# nusense-power-decoupling.net
KiCad netlist of a schematic drawn in Altium Designer
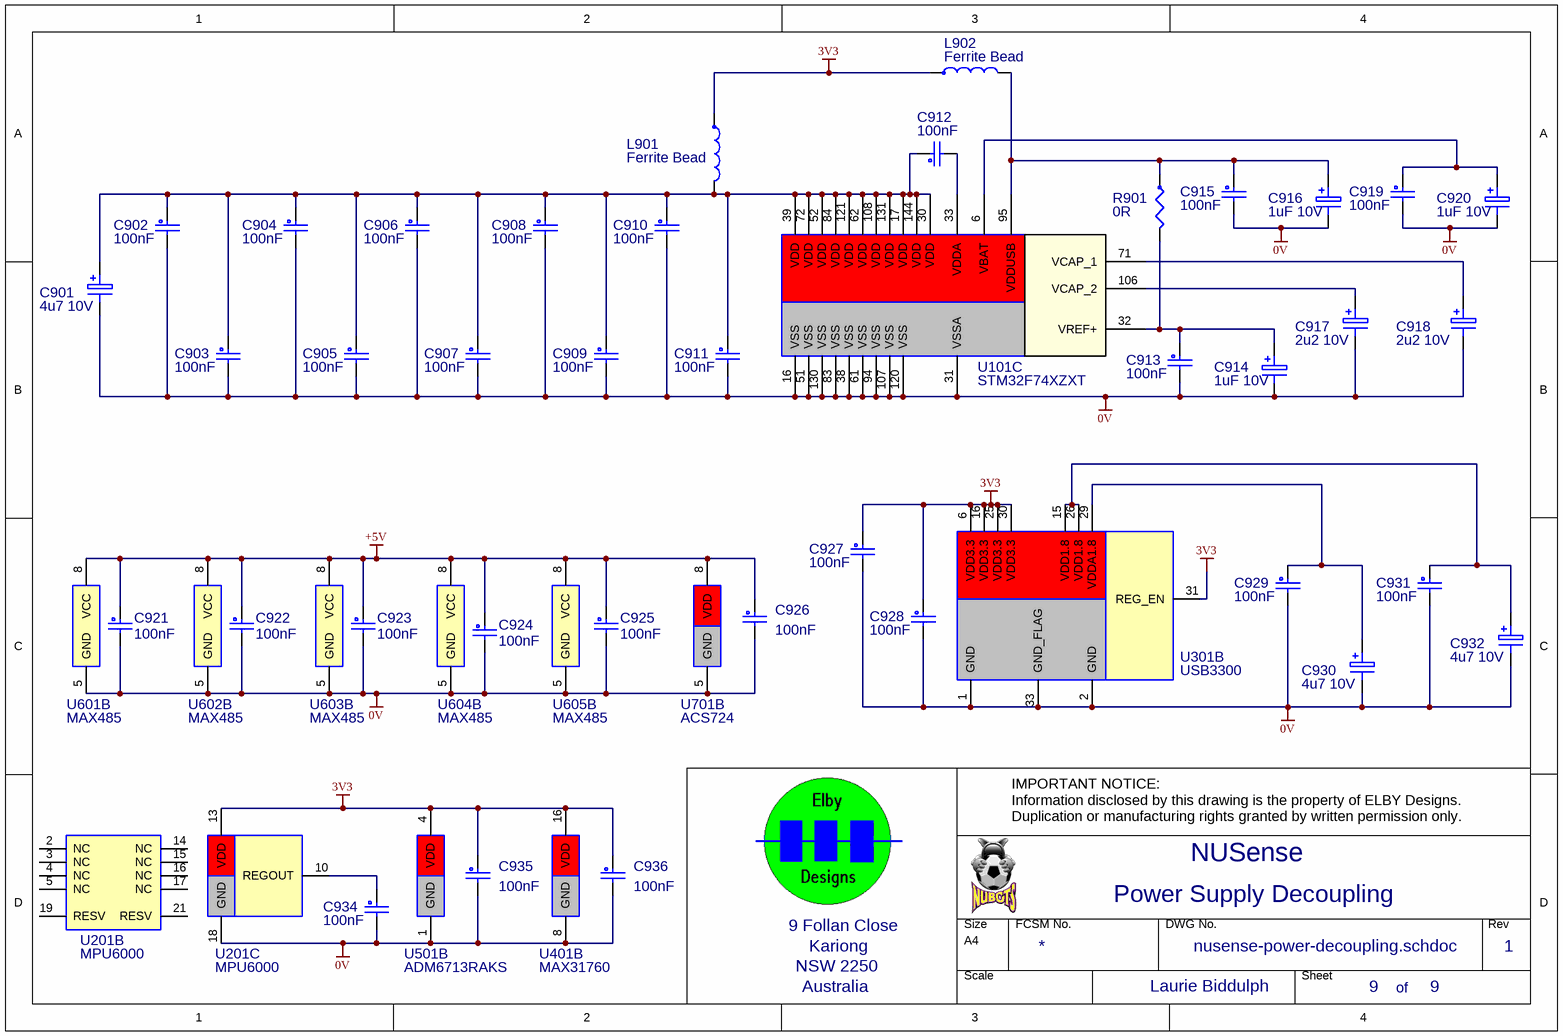
[diagram p0: nusense-power-decoupling.schdoc]

(export (version "E")
  (design (tool "Eeschema 10.0.6"))
  (components
    (comp (ref "C901")
      (value "4u7 10V")
      (footprint "RB-D5.0-P2.0")
      (description "20% 50V Aluminium Electrolytic")
      (libsource (lib "capacitor") (part "CE-4U7F50V(LB)"))
    )
    (comp (ref "C902")
      (value "100nF")
      (footprint "RAD-0.2N(LB)")
      (description "Monolithic Ceramic")
      (libsource (lib "capacitor") (part "CC-100NF(LB)"))
    )
    (comp (ref "C903")
      (value "100nF")
      (footprint "RAD-0.2N(LB)")
      (description "Monolithic Ceramic")
      (libsource (lib "capacitor") (part "CC-100NF(LB)"))
    )
    (comp (ref "C904")
      (value "100nF")
      (footprint "RAD-0.2N(LB)")
      (description "Monolithic Ceramic")
      (libsource (lib "capacitor") (part "CC-100NF(LB)"))
    )
    (comp (ref "C905")
      (value "100nF")
      (footprint "RAD-0.2N(LB)")
      (description "Monolithic Ceramic")
      (libsource (lib "capacitor") (part "CC-100NF(LB)"))
    )
    (comp (ref "C906")
      (value "100nF")
      (footprint "RAD-0.2N(LB)")
      (description "Monolithic Ceramic")
      (libsource (lib "capacitor") (part "CC-100NF(LB)"))
    )
    (comp (ref "C907")
      (value "100nF")
      (footprint "RAD-0.2N(LB)")
      (description "Monolithic Ceramic")
      (libsource (lib "capacitor") (part "CC-100NF(LB)"))
    )
    (comp (ref "C908")
      (value "100nF")
      (footprint "RAD-0.2N(LB)")
      (description "Monolithic Ceramic")
      (libsource (lib "capacitor") (part "CC-100NF(LB)"))
    )
    (comp (ref "C909")
      (value "100nF")
      (footprint "RAD-0.2N(LB)")
      (description "Monolithic Ceramic")
      (libsource (lib "capacitor") (part "CC-100NF(LB)"))
    )
    (comp (ref "C910")
      (value "100nF")
      (footprint "RAD-0.2N(LB)")
      (description "Monolithic Ceramic")
      (libsource (lib "capacitor") (part "CC-100NF(LB)"))
    )
    (comp (ref "C911")
      (value "100nF")
      (footprint "RAD-0.2N(LB)")
      (description "Monolithic Ceramic")
      (libsource (lib "capacitor") (part "CC-100NF(LB)"))
    )
    (comp (ref "C912")
      (value "100nF")
      (footprint "RAD-0.2N(LB)")
      (description "Monolithic Ceramic")
      (libsource (lib "capacitor") (part "CC-100NF(LB)"))
    )
    (comp (ref "C913")
      (value "100nF")
      (footprint "RAD-0.2N(LB)")
      (description "Monolithic Ceramic")
      (libsource (lib "capacitor") (part "CC-100NF(LB)"))
    )
    (comp (ref "C914")
      (value "1uF 10V")
      (footprint "RB-D5.0-P2.0")
      (description "20% 50V Aluminium Electrolytic")
      (libsource (lib "capacitor") (part "CE-1UF50V(LB)"))
    )
    (comp (ref "C915")
      (value "100nF")
      (footprint "RAD-0.2N(LB)")
      (description "Monolithic Ceramic")
      (libsource (lib "capacitor") (part "CC-100NF(LB)"))
    )
    (comp (ref "C916")
      (value "1uF 10V")
      (footprint "RB-D5.0-P2.0")
      (description "20% 50V Aluminium Electrolytic")
      (libsource (lib "capacitor") (part "CE-1UF50V(LB)"))
    )
    (comp (ref "C917")
      (value "2u2 10V")
      (footprint "RB-D5.0-P2.0")
      (description "20% 50V Aluminium Electrolytic")
      (libsource (lib "capacitor") (part "CE-2U2F50V(LB)"))
    )
    (comp (ref "C918")
      (value "2u2 10V")
      (footprint "RB-D5.0-P2.0")
      (description "20% 50V Aluminium Electrolytic")
      (libsource (lib "capacitor") (part "CE-2U2F50V(LB)"))
    )
    (comp (ref "C919")
      (value "100nF")
      (footprint "RAD-0.2N(LB)")
      (description "Monolithic Ceramic")
      (libsource (lib "capacitor") (part "CC-100NF(LB)"))
    )
    (comp (ref "C920")
      (value "1uF 10V")
      (footprint "RB-D5.0-P2.0")
      (description "20% 50V Aluminium Electrolytic")
      (libsource (lib "capacitor") (part "CE-1UF50V(LB)"))
    )
    (comp (ref "C921")
      (value "100nF")
      (footprint "RAD-0.2N(LB)")
      (description "Monolithic Ceramic")
      (libsource (lib "capacitor") (part "CC-100NF(LB)"))
    )
    (comp (ref "C922")
      (value "100nF")
      (footprint "RAD-0.2N(LB)")
      (description "Monolithic Ceramic")
      (libsource (lib "capacitor") (part "CC-100NF(LB)"))
    )
    (comp (ref "C923")
      (value "100nF")
      (footprint "RAD-0.2N(LB)")
      (description "Monolithic Ceramic")
      (libsource (lib "capacitor") (part "CC-100NF(LB)"))
    )
    (comp (ref "C924")
      (value "100nF")
      (footprint "RAD-0.2N(LB)")
      (description "Monolithic Ceramic")
      (libsource (lib "capacitor") (part "CC-100NF(LB)"))
    )
    (comp (ref "C925")
      (value "100nF")
      (footprint "RAD-0.2N(LB)")
      (description "Monolithic Ceramic")
      (libsource (lib "capacitor") (part "CC-100NF(LB)"))
    )
    (comp (ref "C926")
      (value "100nF")
      (footprint "RAD-0.2N(LB)")
      (description "Monolithic Ceramic")
      (libsource (lib "capacitor") (part "CC-100NF(LB)"))
    )
    (comp (ref "C927")
      (value "100nF")
      (footprint "RAD-0.2N(LB)")
      (description "Monolithic Ceramic")
      (libsource (lib "capacitor") (part "CC-100NF(LB)"))
    )
    (comp (ref "C928")
      (value "100nF")
      (footprint "RAD-0.2N(LB)")
      (description "Monolithic Ceramic")
      (libsource (lib "capacitor") (part "CC-100NF(LB)"))
    )
    (comp (ref "C929")
      (value "100nF")
      (footprint "RAD-0.2N(LB)")
      (description "Monolithic Ceramic")
      (libsource (lib "capacitor") (part "CC-100NF(LB)"))
    )
    (comp (ref "C930")
      (value "4u7 10V")
      (footprint "RB-D5.0-P2.0")
      (description "20% 50V Aluminium Electrolytic")
      (libsource (lib "capacitor") (part "CE-4U7F50V(LB)"))
    )
    (comp (ref "C931")
      (value "100nF")
      (footprint "RAD-0.2N(LB)")
      (description "Monolithic Ceramic")
      (libsource (lib "capacitor") (part "CC-100NF(LB)"))
    )
    (comp (ref "C932")
      (value "4u7 10V")
      (footprint "RB-D5.0-P2.0")
      (description "20% 50V Aluminium Electrolytic")
      (libsource (lib "capacitor") (part "CE-4U7F50V(LB)"))
    )
    (comp (ref "C934")
      (value "100nF")
      (footprint "RAD-0.2N(LB)")
      (description "Monolithic Ceramic")
      (libsource (lib "capacitor") (part "CC-100NF(LB)"))
    )
    (comp (ref "C935")
      (value "100nF")
      (footprint "RAD-0.2N(LB)")
      (description "Monolithic Ceramic")
      (libsource (lib "capacitor") (part "CC-100NF(LB)"))
    )
    (comp (ref "C936")
      (value "100nF")
      (footprint "RAD-0.2N(LB)")
      (description "Monolithic Ceramic")
      (libsource (lib "capacitor") (part "CC-100NF(LB)"))
    )
    (comp (ref "L901")
      (value "Ferrite Bead")
      (footprint "AXIAL-0.3IND(LB)")
      (libsource (lib "") (part "FERRITE-BEAD(LB)_1"))
    )
    (comp (ref "L902")
      (value "Ferrite Bead")
      (footprint "AXIAL-0.3IND(LB)")
      (libsource (lib "passive") (part "FERRITE-BEAD(LB)"))
    )
    (comp (ref "R901")
      (value "0R")
      (footprint "AXIAL-0.4(LB)")
      (description "Resistor - Short Circuit")
      (libsource (lib "resistor") (part "RM-SC(LB)"))
    )
    (comp (ref "U101")
      (value "STM32F74XZXT")
      (footprint "LQFP-144_20X20mm")
      (description "32-bit Microcontroller")
      (fields
        (field (name "MANUFACTURER_PART_NUMBER") "stm32f74xzxt")
        (field (name "COPYRIGHT") "Copyright (C) 2016 Accelerated Designs. All rights reserved")
      )
      (libsource (lib "NuBots") (part "STM32F74XZXT"))
    )
    (comp (ref "U201")
      (value "MPU6000")
      (description "Motion Tracking")
      (libsource (lib "NuBots") (part "MPU6000"))
    )
    (comp (ref "U301")
      (value "USB3300")
      (footprint "QFN-32_L")
      (description "USB Host Controller")
      (libsource (lib "NuBots") (part "USB3300"))
    )
    (comp (ref "U401")
      (value "MAX31760")
      (description "Precision Fan Speed")
      (libsource (lib "NuBots") (part "MAX31760"))
    )
    (comp (ref "U501") (value "ADM6713RAKS") (libsource (lib "NuBots") (part "ADM6713")))
    (comp (ref "U601")
      (value "MAX485")
      (footprint "DIP-8(LB)")
      (description "Low-power, Slew-rate limited RS485/RS422 Transceiver")
      (libsource (lib "ic") (part "MAX485(LB)"))
    )
    (comp (ref "U602")
      (value "MAX485")
      (footprint "DIP-8(LB)")
      (description "Low-power, Slew-rate limited RS485/RS422 Transceiver")
      (libsource (lib "ic") (part "MAX485(LB)"))
    )
    (comp (ref "U603")
      (value "MAX485")
      (footprint "DIP-8(LB)")
      (description "Low-power, Slew-rate limited RS485/RS422 Transceiver")
      (libsource (lib "ic") (part "MAX485(LB)"))
    )
    (comp (ref "U604")
      (value "MAX485")
      (footprint "DIP-8(LB)")
      (description "Low-power, Slew-rate limited RS485/RS422 Transceiver")
      (libsource (lib "ic") (part "MAX485(LB)"))
    )
    (comp (ref "U605")
      (value "MAX485")
      (footprint "DIP-8(LB)")
      (description "Low-power, Slew-rate limited RS485/RS422 Transceiver")
      (libsource (lib "ic") (part "MAX485(LB)"))
    )
    (comp (ref "U701")
      (value "ACS724")
      (description "Current Monitor")
      (libsource (lib "NuBots") (part "ACS724"))
    )
  )
  (nets
    (net (code "1") (name "+5V") (class "Default")
      (node (ref "C921") (pin "1") (pintype "passive"))
      (node (ref "C922") (pin "1") (pintype "passive"))
      (node (ref "C923") (pin "1") (pintype "passive"))
      (node (ref "C924") (pin "1") (pintype "passive"))
      (node (ref "C925") (pin "1") (pintype "passive"))
      (node (ref "C926") (pin "1") (pintype "passive"))
      (node (ref "U601") (pin "8") (pinfunction "VCC_8") (pintype "power_in"))
      (node (ref "U602") (pin "8") (pinfunction "VCC_8") (pintype "power_in"))
      (node (ref "U603") (pin "8") (pinfunction "VCC_8") (pintype "power_in"))
      (node (ref "U604") (pin "8") (pinfunction "VCC_8") (pintype "power_in"))
      (node (ref "U605") (pin "8") (pinfunction "VCC_8") (pintype "power_in"))
      (node (ref "U701") (pin "8") (pinfunction "VDD_8") (pintype "power_in"))
    )
    (net (code "2") (name "0V") (class "Default")
      (node (ref "C901") (pin "2") (pintype "passive"))
      (node (ref "C902") (pin "2") (pintype "passive"))
      (node (ref "C903") (pin "2") (pintype "passive"))
      (node (ref "C904") (pin "2") (pintype "passive"))
      (node (ref "C905") (pin "2") (pintype "passive"))
      (node (ref "C906") (pin "2") (pintype "passive"))
      (node (ref "C907") (pin "2") (pintype "passive"))
      (node (ref "C908") (pin "2") (pintype "passive"))
      (node (ref "C909") (pin "2") (pintype "passive"))
      (node (ref "C910") (pin "2") (pintype "passive"))
      (node (ref "C911") (pin "2") (pintype "passive"))
      (node (ref "C913") (pin "2") (pintype "passive"))
      (node (ref "C914") (pin "2") (pintype "passive"))
      (node (ref "C915") (pin "2") (pintype "passive"))
      (node (ref "C916") (pin "2") (pintype "passive"))
      (node (ref "C917") (pin "2") (pintype "passive"))
      (node (ref "C918") (pin "2") (pintype "passive"))
      (node (ref "C919") (pin "2") (pintype "passive"))
      (node (ref "C920") (pin "2") (pintype "passive"))
      (node (ref "C921") (pin "2") (pintype "passive"))
      (node (ref "C922") (pin "2") (pintype "passive"))
      (node (ref "C923") (pin "2") (pintype "passive"))
      (node (ref "C924") (pin "2") (pintype "passive"))
      (node (ref "C925") (pin "2") (pintype "passive"))
      (node (ref "C926") (pin "2") (pintype "passive"))
      (node (ref "C927") (pin "2") (pintype "passive"))
      (node (ref "C928") (pin "2") (pintype "passive"))
      (node (ref "C929") (pin "2") (pintype "passive"))
      (node (ref "C930") (pin "2") (pintype "passive"))
      (node (ref "C931") (pin "2") (pintype "passive"))
      (node (ref "C932") (pin "2") (pintype "passive"))
      (node (ref "C934") (pin "2") (pintype "passive"))
      (node (ref "C935") (pin "2") (pintype "passive"))
      (node (ref "C936") (pin "2") (pintype "passive"))
      (node (ref "U101") (pin "107") (pinfunction "VSS_107") (pintype "power_in"))
      (node (ref "U101") (pin "120") (pinfunction "VSS_120") (pintype "power_in"))
      (node (ref "U101") (pin "130") (pinfunction "VSS_130") (pintype "power_in"))
      (node (ref "U101") (pin "16") (pinfunction "VSS_16") (pintype "power_in"))
      (node (ref "U101") (pin "31") (pinfunction "VSSA_31") (pintype "power_in"))
      (node (ref "U101") (pin "38") (pinfunction "VSS_38") (pintype "power_in"))
      (node (ref "U101") (pin "51") (pinfunction "VSS_51") (pintype "power_in"))
      (node (ref "U101") (pin "61") (pinfunction "VSS_61") (pintype "power_in"))
      (node (ref "U101") (pin "83") (pinfunction "VSS_83") (pintype "power_in"))
      (node (ref "U101") (pin "94") (pinfunction "VSS_94") (pintype "power_in"))
      (node (ref "U201") (pin "18") (pinfunction "GND_18") (pintype "power_in"))
      (node (ref "U301") (pin "1") (pinfunction "GND_1") (pintype "power_in"))
      (node (ref "U301") (pin "2") (pinfunction "GND_2") (pintype "power_in"))
      (node (ref "U301") (pin "33") (pinfunction "GND_FLAG_33") (pintype "power_in"))
      (node (ref "U401") (pin "8") (pinfunction "GND_8") (pintype "power_in"))
      (node (ref "U501") (pin "1") (pinfunction "GND_1") (pintype "power_in"))
      (node (ref "U601") (pin "5") (pinfunction "GND_5") (pintype "power_in"))
      (node (ref "U602") (pin "5") (pinfunction "GND_5") (pintype "power_in"))
      (node (ref "U603") (pin "5") (pinfunction "GND_5") (pintype "power_in"))
      (node (ref "U604") (pin "5") (pinfunction "GND_5") (pintype "power_in"))
      (node (ref "U605") (pin "5") (pinfunction "GND_5") (pintype "power_in"))
      (node (ref "U701") (pin "5") (pinfunction "GND_5") (pintype "power_in"))
    )
    (net (code "3") (name "3V3") (class "Default")
      (node (ref "C927") (pin "1") (pintype "passive"))
      (node (ref "C928") (pin "1") (pintype "passive"))
      (node (ref "C935") (pin "1") (pintype "passive"))
      (node (ref "C936") (pin "1") (pintype "passive"))
      (node (ref "L901") (pin "1") (pinfunction "1_1") (pintype "passive"))
      (node (ref "L902") (pin "1") (pinfunction "1_1") (pintype "passive"))
      (node (ref "U201") (pin "13") (pinfunction "VDD_13") (pintype "power_in"))
      (node (ref "U301") (pin "16") (pinfunction "VDD3.3_16") (pintype "power_in"))
      (node (ref "U301") (pin "25") (pinfunction "VDD3.3_25") (pintype "power_in"))
      (node (ref "U301") (pin "30") (pinfunction "VDD3.3_30") (pintype "power_in"))
      (node (ref "U301") (pin "31") (pinfunction "REG_EN_31") (pintype "passive"))
      (node (ref "U301") (pin "6") (pinfunction "VDD3.3_6") (pintype "power_in"))
      (node (ref "U401") (pin "16") (pinfunction "VDD_16") (pintype "power_in"))
      (node (ref "U501") (pin "4") (pinfunction "VDD_4") (pintype "power_in"))
    )
    (net (code "4") (name "Net-(C901-Pad1)") (class "Default")
      (node (ref "C901") (pin "1") (pintype "passive"))
      (node (ref "C902") (pin "1") (pintype "passive"))
      (node (ref "C903") (pin "1") (pintype "passive"))
      (node (ref "C904") (pin "1") (pintype "passive"))
      (node (ref "C905") (pin "1") (pintype "passive"))
      (node (ref "C906") (pin "1") (pintype "passive"))
      (node (ref "C907") (pin "1") (pintype "passive"))
      (node (ref "C908") (pin "1") (pintype "passive"))
      (node (ref "C909") (pin "1") (pintype "passive"))
      (node (ref "C910") (pin "1") (pintype "passive"))
      (node (ref "C911") (pin "1") (pintype "passive"))
      (node (ref "C912") (pin "1") (pintype "passive"))
      (node (ref "L901") (pin "2") (pinfunction "2_2") (pintype "passive"))
      (node (ref "U101") (pin "108") (pinfunction "VDD_108") (pintype "power_in"))
      (node (ref "U101") (pin "121") (pinfunction "VDD_121") (pintype "power_in"))
      (node (ref "U101") (pin "131") (pinfunction "VDD_131") (pintype "power_in"))
      (node (ref "U101") (pin "144") (pinfunction "VDD_144") (pintype "power_in"))
      (node (ref "U101") (pin "17") (pinfunction "VDD_17") (pintype "power_in"))
      (node (ref "U101") (pin "30") (pinfunction "VDD_30") (pintype "power_in"))
      (node (ref "U101") (pin "39") (pinfunction "VDD_39") (pintype "power_in"))
      (node (ref "U101") (pin "52") (pinfunction "VDD_52") (pintype "power_in"))
      (node (ref "U101") (pin "62") (pinfunction "VDD_62") (pintype "power_in"))
      (node (ref "U101") (pin "72") (pinfunction "VDD_72") (pintype "power_in"))
      (node (ref "U101") (pin "84") (pinfunction "VDD_84") (pintype "power_in"))
    )
    (net (code "5") (name "Net-(C931-Pad1)") (class "Default")
      (node (ref "C931") (pin "1") (pintype "passive"))
      (node (ref "C932") (pin "1") (pintype "passive"))
      (node (ref "U301") (pin "15") (pinfunction "VDD1.8_15") (pintype "power_in"))
      (node (ref "U301") (pin "26") (pinfunction "VDD1.8_26") (pintype "power_in"))
    )
    (net (code "6") (name "Net-(U101C-VBAT)") (class "Default")
      (node (ref "C919") (pin "1") (pintype "passive"))
      (node (ref "C920") (pin "1") (pintype "passive"))
      (node (ref "U101") (pin "6") (pinfunction "VBAT_6") (pintype "power_in"))
    )
    (net (code "7") (name "Net-(U101C-VCAP_1)") (class "Default")
      (node (ref "C918") (pin "1") (pintype "passive"))
      (node (ref "U101") (pin "71") (pinfunction "VCAP_1_71") (pintype "power_in"))
    )
    (net (code "8") (name "Net-(U101C-VCAP_2)") (class "Default")
      (node (ref "C917") (pin "1") (pintype "passive"))
      (node (ref "U101") (pin "106") (pinfunction "VCAP_2_106") (pintype "power_in"))
    )
    (net (code "9") (name "Net-(U101C-VDDA)") (class "Default")
      (node (ref "C912") (pin "2") (pintype "passive"))
      (node (ref "U101") (pin "33") (pinfunction "VDDA_33") (pintype "power_in"))
    )
    (net (code "10") (name "Net-(U101C-VDDUSB)") (class "Default")
      (node (ref "C915") (pin "1") (pintype "passive"))
      (node (ref "C916") (pin "1") (pintype "passive"))
      (node (ref "L902") (pin "2") (pinfunction "2_2") (pintype "passive"))
      (node (ref "R901") (pin "1") (pinfunction "1_1") (pintype "passive"))
      (node (ref "U101") (pin "95") (pinfunction "VDDUSB_95") (pintype "power_in"))
    )
    (net (code "11") (name "Net-(U101C-VREF+)") (class "Default")
      (node (ref "C913") (pin "1") (pintype "passive"))
      (node (ref "C914") (pin "1") (pintype "passive"))
      (node (ref "R901") (pin "2") (pinfunction "2_2") (pintype "passive"))
      (node (ref "U101") (pin "32") (pinfunction "VREF+_32") (pintype "power_in"))
    )
    (net (code "12") (name "Net-(U201C-REGOUT)") (class "Default")
      (node (ref "C934") (pin "1") (pintype "passive"))
      (node (ref "U201") (pin "10") (pinfunction "REGOUT_10") (pintype "passive"))
    )
    (net (code "13") (name "Net-(U301B-VDDA1.8)") (class "Default")
      (node (ref "C929") (pin "1") (pintype "passive"))
      (node (ref "C930") (pin "1") (pintype "passive"))
      (node (ref "U301") (pin "29") (pinfunction "VDDA1.8_29") (pintype "power_in"))
    )
    (net (code "14") (name "unconnected-(U201B-NC-Pad2)") (class "Default")
      (node (ref "U201") (pin "2") (pinfunction "NC_2") (pintype "passive"))
    )
    (net (code "15") (name "unconnected-(U201B-NC-Pad3)") (class "Default")
      (node (ref "U201") (pin "3") (pinfunction "NC_3") (pintype "passive"))
    )
    (net (code "16") (name "unconnected-(U201B-NC-Pad4)") (class "Default")
      (node (ref "U201") (pin "4") (pinfunction "NC_4") (pintype "passive"))
    )
    (net (code "17") (name "unconnected-(U201B-NC-Pad5)") (class "Default")
      (node (ref "U201") (pin "5") (pinfunction "NC_5") (pintype "passive"))
    )
    (net (code "18") (name "unconnected-(U201B-NC-Pad14)") (class "Default")
      (node (ref "U201") (pin "14") (pinfunction "NC_14") (pintype "passive"))
    )
    (net (code "19") (name "unconnected-(U201B-NC-Pad15)") (class "Default")
      (node (ref "U201") (pin "15") (pinfunction "NC_15") (pintype "passive"))
    )
    (net (code "20") (name "unconnected-(U201B-NC-Pad16)") (class "Default")
      (node (ref "U201") (pin "16") (pinfunction "NC_16") (pintype "passive"))
    )
    (net (code "21") (name "unconnected-(U201B-NC-Pad17)") (class "Default")
      (node (ref "U201") (pin "17") (pinfunction "NC_17") (pintype "passive"))
    )
    (net (code "22") (name "unconnected-(U201B-RESV-Pad19)") (class "Default")
      (node (ref "U201") (pin "19") (pinfunction "RESV_19") (pintype "passive"))
    )
    (net (code "23") (name "unconnected-(U201B-RESV-Pad21)") (class "Default")
      (node (ref "U201") (pin "21") (pinfunction "RESV_21") (pintype "passive"))
    )
  )
)
